# 6_-_COMMUNICATIONS.net
KiCad netlist of a schematic drawn in Altium Designer
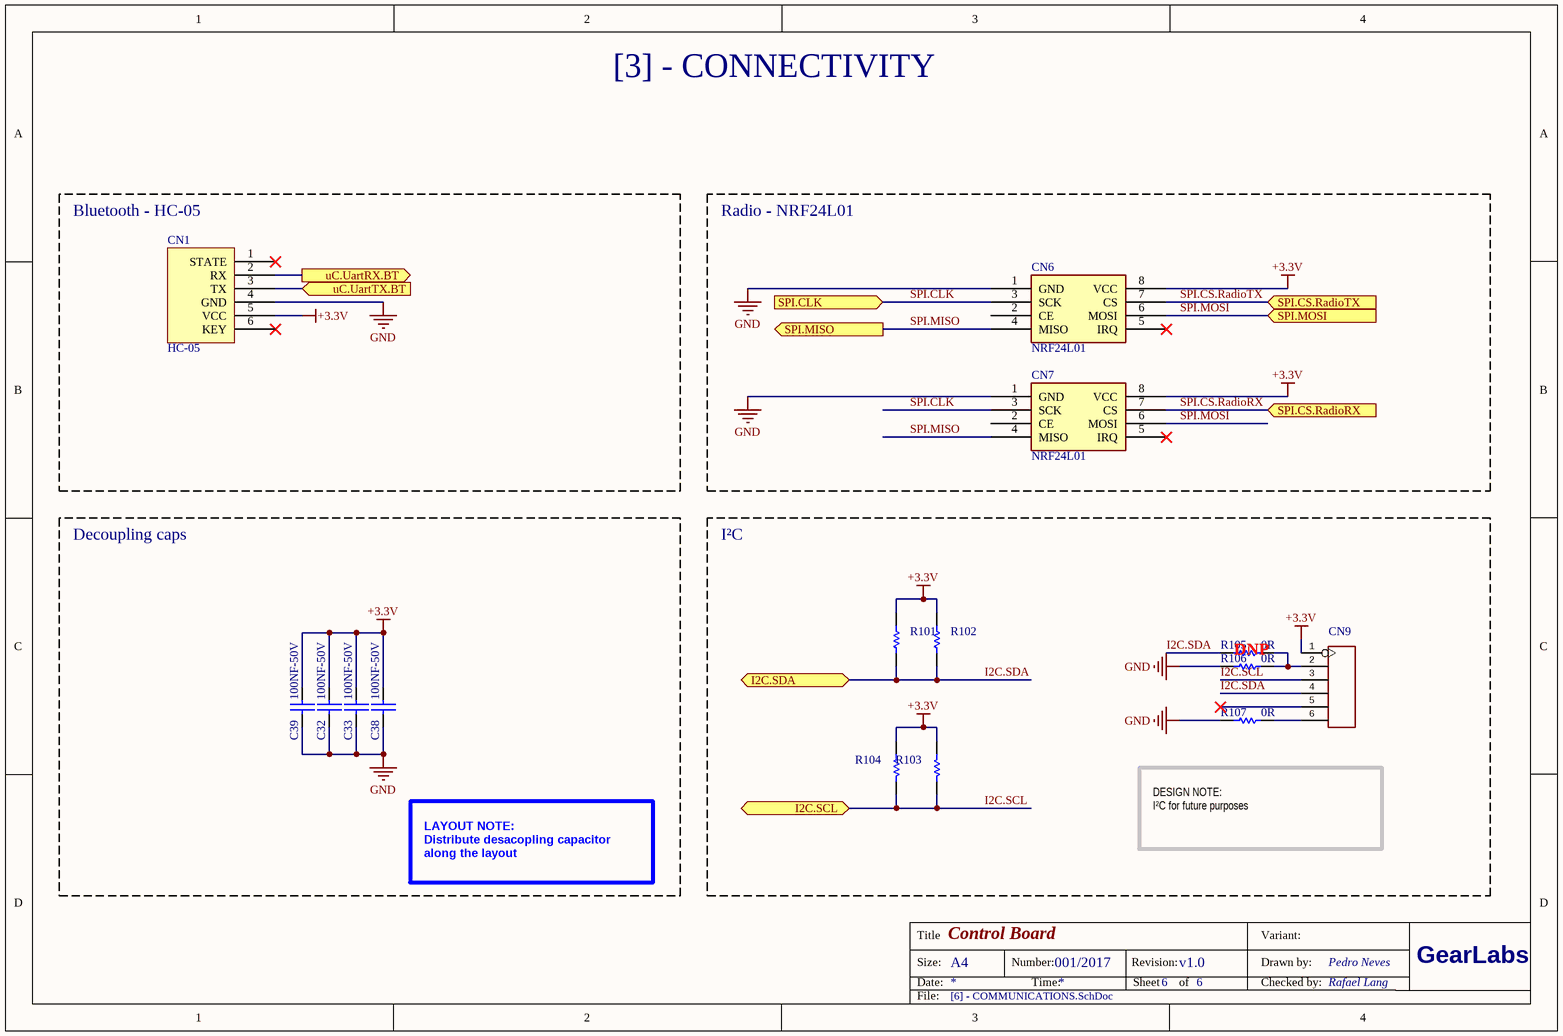
[diagram p0: [6] - COMMUNICATIONS.SchDoc]

(export (version "E")
  (design (tool "Eeschema 10.0.6"))
  (components
    (comp (ref "C32")
      (value "100NF-50V")
      (footprint "C0603")
      (fields (field (name "MPN") "CC0603KRX7R9BB104") (field (name "Comment") "302010138"))
      (libsource (lib "Seeed-Capacitor") (part "CERAMIC-100NF-50V-10%-X7R(0603)"))
    )
    (comp (ref "C33")
      (value "100NF-50V")
      (footprint "C0603")
      (fields (field (name "MPN") "CC0603KRX7R9BB104") (field (name "Comment") "302010138"))
      (libsource (lib "Seeed-Capacitor") (part "CERAMIC-100NF-50V-10%-X7R(0603)"))
    )
    (comp (ref "C38")
      (value "100NF-50V")
      (footprint "C0603")
      (fields (field (name "MPN") "CC0603KRX7R9BB104") (field (name "Comment") "302010138"))
      (libsource (lib "Seeed-Capacitor") (part "CERAMIC-100NF-50V-10%-X7R(0603)"))
    )
    (comp (ref "C39")
      (value "100NF-50V")
      (footprint "C0603")
      (fields (field (name "MPN") "CC0603KRX7R9BB104") (field (name "Comment") "302010138"))
      (libsource (lib "Seeed-Capacitor") (part "CERAMIC-100NF-50V-10%-X7R(0603)"))
    )
    (comp (ref "CN1") (value "HC-05") (footprint "HC-05") (libsource (lib "Diversos") (part "HC-05")))
    (comp (ref "CN6")
      (value "NRF24L01")
      (footprint "NRF24l01")
      (libsource (lib "Diversos") (part "NRF24L01"))
    )
    (comp (ref "CN7")
      (value "NRF24L01")
      (footprint "NRF24l01")
      (libsource (lib "Diversos") (part "NRF24L01"))
    )
    (comp (ref "CN9")
      (value "320030060")
      (footprint "H6-2.54")
      (fields (field (name "MPN") "F185-1106A1BSYC1"))
      (libsource (lib "Seeed-Connector") (part "DIP-BLACK-FEMALE-HEADER-VERT(6P-2.54)"))
    )
    (comp (ref "R101")
      (value "301010299")
      (footprint "R0603")
      (fields (field (name "MPN") "RC0603FR-0710KL"))
      (libsource (lib "Seeed-Resistor") (part "SMD-RES-10K-1%-1/10W(0603)"))
    )
    (comp (ref "R102")
      (value "301010299")
      (footprint "R0603")
      (fields (field (name "MPN") "RC0603FR-0710KL"))
      (libsource (lib "Seeed-Resistor") (part "SMD-RES-10K-1%-1/10W(0603)"))
    )
    (comp (ref "R103")
      (value "301010299")
      (footprint "R0603")
      (fields (field (name "MPN") "RC0603FR-0710KL"))
      (libsource (lib "Seeed-Resistor") (part "SMD-RES-10K-1%-1/10W(0603)"))
    )
    (comp (ref "R104")
      (value "301010299")
      (footprint "R0603")
      (fields (field (name "MPN") "RC0603FR-0710KL"))
      (libsource (lib "Seeed-Resistor") (part "SMD-RES-10K-1%-1/10W(0603)"))
    )
    (comp (ref "R105")
      (value "0R")
      (footprint "R0603")
      (fields (field (name "MPN") "RC0603JR-070RL") (field (name "Comment") "301010292"))
      (libsource (lib "Seeed-Resistor") (part "SMD-RES-0R-5%-1/10W(0603)"))
    )
    (comp (ref "R106")
      (value "0R")
      (footprint "R0603")
      (fields (field (name "MPN") "RC0603JR-070RL") (field (name "Comment") "301010292"))
      (libsource (lib "Seeed-Resistor") (part "SMD-RES-0R-5%-1/10W(0603)"))
    )
    (comp (ref "R107")
      (value "0R")
      (footprint "R0603")
      (fields (field (name "MPN") "RC0603JR-070RL") (field (name "Comment") "301010292"))
      (libsource (lib "Seeed-Resistor") (part "SMD-RES-0R-5%-1/10W(0603)"))
    )
  )
  (nets
    (net (code "1") (name "+3.3V") (class "Default")
      (node (ref "C32") (pin "1") (pinfunction "1_1") (pintype "passive"))
      (node (ref "C33") (pin "1") (pinfunction "1_1") (pintype "passive"))
      (node (ref "C38") (pin "1") (pinfunction "1_1") (pintype "passive"))
      (node (ref "C39") (pin "1") (pinfunction "1_1") (pintype "passive"))
      (node (ref "CN1") (pin "5") (pinfunction "VCC_5") (pintype "passive"))
      (node (ref "CN6") (pin "8") (pinfunction "VCC_8") (pintype "passive"))
      (node (ref "CN7") (pin "8") (pinfunction "VCC_8") (pintype "passive"))
      (node (ref "CN9") (pin "1") (pinfunction "1_1") (pintype "passive"))
      (node (ref "R101") (pin "2") (pinfunction "2_2") (pintype "passive"))
      (node (ref "R102") (pin "2") (pinfunction "2_2") (pintype "passive"))
      (node (ref "R103") (pin "2") (pinfunction "2_2") (pintype "passive"))
      (node (ref "R104") (pin "2") (pinfunction "2_2") (pintype "passive"))
    )
    (net (code "2") (name "/I2C.SCL") (class "Default")
      (node (ref "CN9") (pin "3") (pinfunction "3_3") (pintype "passive"))
      (node (ref "R103") (pin "1") (pinfunction "1_1") (pintype "passive"))
      (node (ref "R104") (pin "1") (pinfunction "1_1") (pintype "passive"))
    )
    (net (code "3") (name "/I2C.SDA") (class "Default")
      (node (ref "CN9") (pin "4") (pinfunction "4_4") (pintype "passive"))
      (node (ref "R101") (pin "1") (pinfunction "1_1") (pintype "passive"))
      (node (ref "R102") (pin "1") (pinfunction "1_1") (pintype "passive"))
      (node (ref "R105") (pin "1") (pinfunction "1_1") (pintype "passive"))
    )
    (net (code "4") (name "/SPI.CLK") (class "Default")
      (node (ref "CN6") (pin "3") (pinfunction "SCK_3") (pintype "passive"))
      (node (ref "CN7") (pin "3") (pinfunction "SCK_3") (pintype "passive"))
    )
    (net (code "5") (name "/SPI.CS.RadioRX") (class "Default")
      (node (ref "CN7") (pin "7") (pinfunction "CS_7") (pintype "passive"))
    )
    (net (code "6") (name "/SPI.CS.RadioTX") (class "Default")
      (node (ref "CN6") (pin "7") (pinfunction "CS_7") (pintype "passive"))
    )
    (net (code "7") (name "/SPI.MISO") (class "Default")
      (node (ref "CN6") (pin "4") (pinfunction "MISO_4") (pintype "passive"))
      (node (ref "CN7") (pin "4") (pinfunction "MISO_4") (pintype "passive"))
    )
    (net (code "8") (name "/SPI.MOSI") (class "Default")
      (node (ref "CN6") (pin "6") (pinfunction "MOSI_6") (pintype "passive"))
      (node (ref "CN7") (pin "6") (pinfunction "MOSI_6") (pintype "passive"))
    )
    (net (code "9") (name "/uC.UartRX.BT") (class "Default")
      (node (ref "CN1") (pin "2") (pinfunction "RX_2") (pintype "passive"))
    )
    (net (code "10") (name "/uC.UartTX.BT") (class "Default")
      (node (ref "CN1") (pin "3") (pinfunction "TX_3") (pintype "passive"))
    )
    (net (code "11") (name "GND") (class "Default")
      (node (ref "C32") (pin "2") (pinfunction "2_2") (pintype "passive"))
      (node (ref "C33") (pin "2") (pinfunction "2_2") (pintype "passive"))
      (node (ref "C38") (pin "2") (pinfunction "2_2") (pintype "passive"))
      (node (ref "C39") (pin "2") (pinfunction "2_2") (pintype "passive"))
      (node (ref "CN1") (pin "4") (pinfunction "GND_4") (pintype "passive"))
      (node (ref "CN6") (pin "1") (pinfunction "GND_1") (pintype "passive"))
      (node (ref "CN7") (pin "1") (pinfunction "GND_1") (pintype "passive"))
      (node (ref "R106") (pin "1") (pinfunction "1_1") (pintype "passive"))
      (node (ref "R107") (pin "1") (pinfunction "1_1") (pintype "passive"))
    )
    (net (code "12") (name "Net-(CN9-Pad2)") (class "Default")
      (node (ref "CN9") (pin "2") (pinfunction "2_2") (pintype "passive"))
      (node (ref "R105") (pin "2") (pinfunction "2_2") (pintype "passive"))
      (node (ref "R106") (pin "2") (pinfunction "2_2") (pintype "passive"))
    )
    (net (code "13") (name "Net-(CN9-Pad6)") (class "Default")
      (node (ref "CN9") (pin "6") (pinfunction "6_6") (pintype "passive"))
      (node (ref "R107") (pin "2") (pinfunction "2_2") (pintype "passive"))
    )
    (net (code "14") (name "unconnected-(CN1-KEY-Pad6)") (class "Default")
      (node (ref "CN1") (pin "6") (pinfunction "KEY_6") (pintype "passive+no_connect"))
    )
    (net (code "15") (name "unconnected-(CN1-STATE-Pad1)") (class "Default")
      (node (ref "CN1") (pin "1") (pinfunction "STATE_1") (pintype "passive+no_connect"))
    )
    (net (code "16") (name "unconnected-(CN6-CE-Pad2)") (class "Default")
      (node (ref "CN6") (pin "2") (pinfunction "CE_2") (pintype "passive"))
    )
    (net (code "17") (name "unconnected-(CN6-IRQ-Pad5)") (class "Default")
      (node (ref "CN6") (pin "5") (pinfunction "IRQ_5") (pintype "passive+no_connect"))
    )
    (net (code "18") (name "unconnected-(CN7-CE-Pad2)") (class "Default")
      (node (ref "CN7") (pin "2") (pinfunction "CE_2") (pintype "passive"))
    )
    (net (code "19") (name "unconnected-(CN7-IRQ-Pad5)") (class "Default")
      (node (ref "CN7") (pin "5") (pinfunction "IRQ_5") (pintype "passive+no_connect"))
    )
    (net (code "20") (name "unconnected-(CN9-Pad5)") (class "Default")
      (node (ref "CN9") (pin "5") (pinfunction "5_5") (pintype "passive+no_connect"))
    )
  )
)
